# mcu.net
KiCad netlist of a schematic drawn in Altium Designer
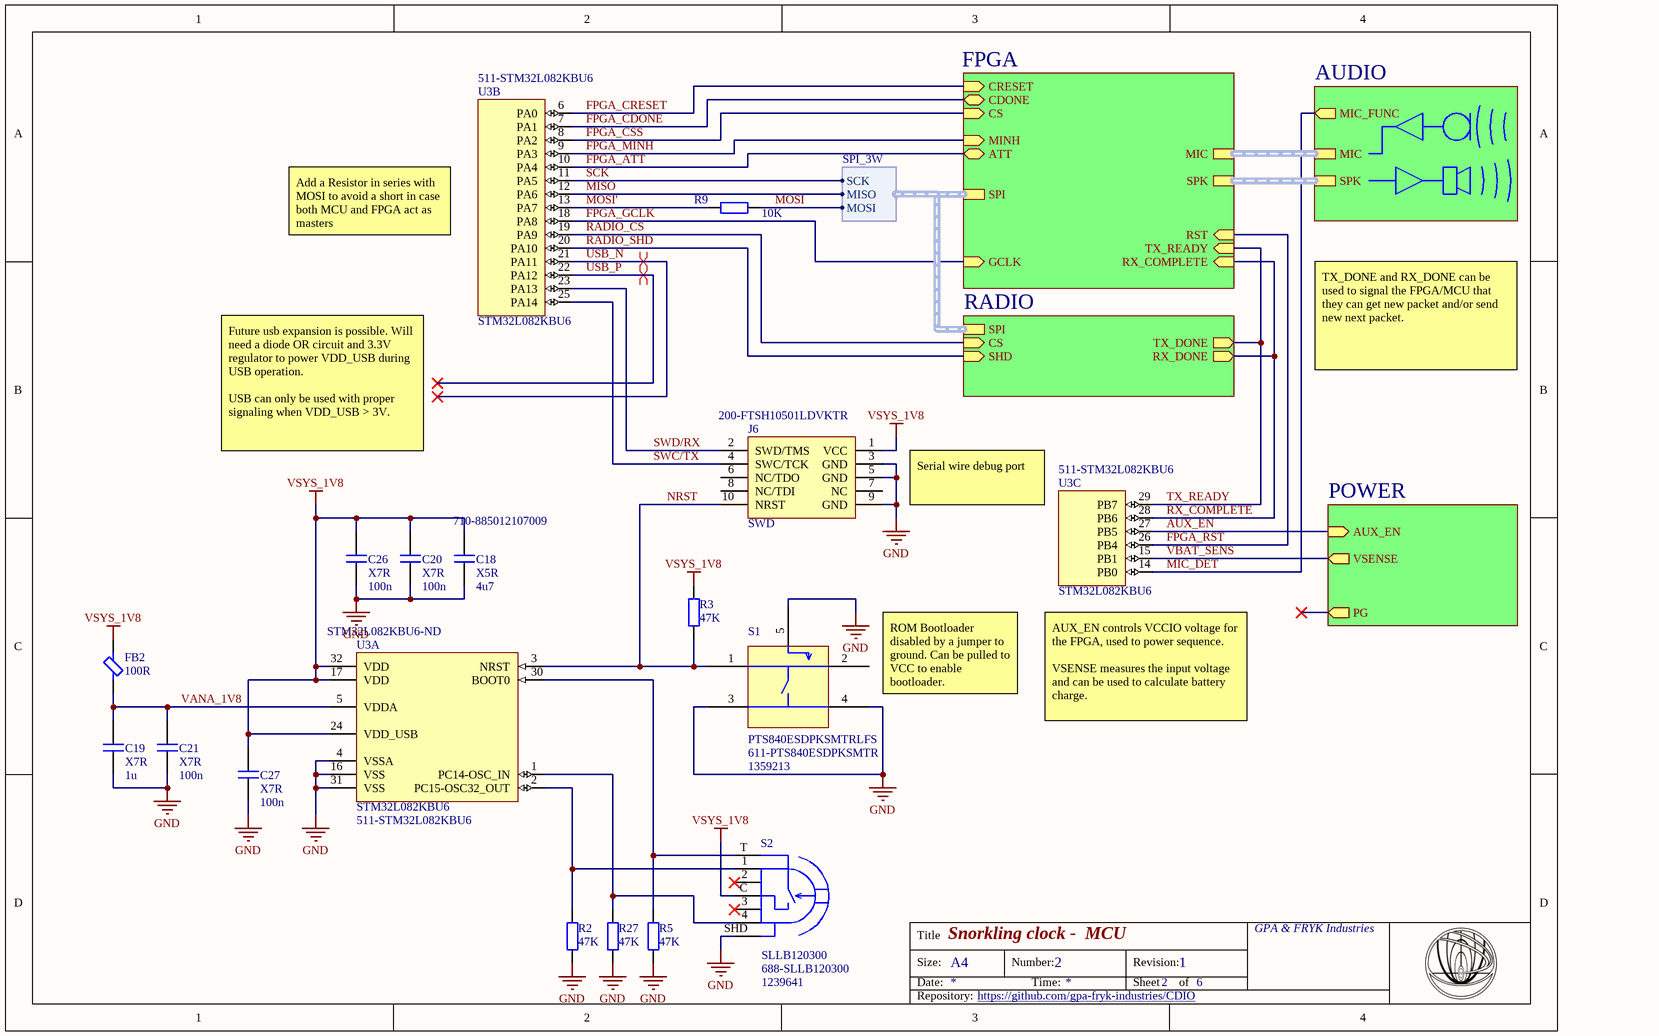
[diagram p0: mcu.SchDoc]

(export (version "E")
  (design (tool "Eeschema 10.0.6"))
  (components
    (comp (ref "C18")
      (value "4u7")
      (footprint "CAPC2012X11N")
      (description "Capacitor")
      (fields
        (field (name "TYPE") "X5R")
        (field (name "SUPPLIER PART NUMBER 1") "710-885012107009")
        (field (name "Comment") "cap")
      )
      (libsource (lib "lib_passives") (part "cap"))
    )
    (comp (ref "C19")
      (value "1u")
      (footprint "CAPC2012X11N")
      (description "Capacitor")
      (fields (field (name "TYPE") "X7R") (field (name "Comment") "cap"))
      (libsource (lib "lib_passives") (part "cap"))
    )
    (comp (ref "C20")
      (value "100n")
      (footprint "CAPC1005X06N")
      (description "Capacitor")
      (fields (field (name "TYPE") "X7R") (field (name "Comment") "cap"))
      (libsource (lib "lib_passives") (part "cap"))
    )
    (comp (ref "C21")
      (value "100n")
      (footprint "CAPC1005X06N")
      (description "Capacitor")
      (fields (field (name "TYPE") "X7R") (field (name "Comment") "cap"))
      (libsource (lib "lib_passives") (part "cap"))
    )
    (comp (ref "C26")
      (value "100n")
      (footprint "CAPC1005X06N")
      (description "Capacitor")
      (fields (field (name "TYPE") "X7R") (field (name "Comment") "cap"))
      (libsource (lib "lib_passives") (part "cap"))
    )
    (comp (ref "C27")
      (value "100n")
      (footprint "CAPC1005X06N")
      (description "Capacitor")
      (fields (field (name "TYPE") "X7R") (field (name "Comment") "cap"))
      (libsource (lib "lib_passives") (part "cap"))
    )
    (comp (ref "FB2")
      (value "100R")
      (footprint "INDC1005X06N")
      (description "Inductor")
      (fields (field (name "Comment") "ferrite"))
      (libsource (lib "lib_passives") (part "ferrite"))
    )
    (comp (ref "J6")
      (value "SWD")
      (footprint "hdr_2x5_50mil")
      (description "SWD Header")
      (fields (field (name "SUPPLIER PART NUMBER 1") "200-FTSH10501LDVKTR"))
      (libsource (lib "lib_connectors") (part "hdr_swd"))
    )
    (comp (ref "R2")
      (value "47K")
      (footprint "RESC1005X04N")
      (description "Resistor")
      (fields (field (name "Comment") "res"))
      (libsource (lib "lib_passives") (part "res"))
    )
    (comp (ref "R3")
      (value "47K")
      (footprint "RESC1005X04N")
      (description "Resistor")
      (fields (field (name "Comment") "res"))
      (libsource (lib "lib_passives") (part "res"))
    )
    (comp (ref "R5")
      (value "47K")
      (footprint "RESC1005X04N")
      (description "Resistor")
      (fields (field (name "Comment") "res"))
      (libsource (lib "lib_passives") (part "res"))
    )
    (comp (ref "R9")
      (value "10K")
      (footprint "RESC1005X04N")
      (description "Resistor")
      (fields (field (name "Comment") "res"))
      (libsource (lib "") (part "res_1"))
    )
    (comp (ref "R27")
      (value "47K")
      (footprint "RESC1005X04N")
      (description "Resistor")
      (fields (field (name "Comment") "res"))
      (libsource (lib "lib_passives") (part "res"))
    )
    (comp (ref "S1")
      (value "PTS840ESDPKSMTRLFS")
      (footprint "PCBComponent_1")
      (description "Microminiature SMT Side Actuated tactile switch")
      (fields
        (field (name "SUPPLIER PART NUMBER 1") "611-PTS840ESDPKSMTR")
        (field (name "SUPPLIER PART NUMBER 2") "1359213")
      )
      (libsource (lib "lib_cnk") (part "pts840esdpksmtrlfs"))
    )
    (comp (ref "S2")
      (value "SLLB120300")
      (footprint "sllb120300")
      (description "Compact and low-profile horizontal type for various applications")
      (fields
        (field (name "SUPPLIER PART NUMBER 1") "688-SLLB120300")
        (field (name "SUPPLIER PART NUMBER 2") "1239641")
      )
      (libsource (lib "lib_alps") (part "sllb120300"))
    )
    (comp (ref "U3")
      (value "STM32L082KBU6")
      (footprint "QFN50P500X500X60_HS-33N")
      (fields
        (field (name "SUPPLIER PART NUMBER 1") "511-STM32L082KBU6")
        (field (name "SUPPLIER PART NUMBER 2") "STM32L082KBU6-ND")
      )
      (libsource (lib "") (part "stm32l082kbu6_1"))
    )
  )
  (nets
    (net (code "2") (name "/AUX_EN") (class "Default")
      (node (ref "U3") (pin "27") (pinfunction "PB5_27") (pintype "bidirectional"))
    )
    (net (code "3") (name "/FPGA_ATT") (class "Default")
      (node (ref "U3") (pin "10") (pinfunction "PA4_10") (pintype "bidirectional"))
    )
    (net (code "4") (name "/FPGA_CDONE") (class "Default")
      (node (ref "U3") (pin "7") (pinfunction "PA1_7") (pintype "bidirectional"))
    )
    (net (code "5") (name "/FPGA_CRESET") (class "Default")
      (node (ref "U3") (pin "6") (pinfunction "PA0_6") (pintype "bidirectional"))
    )
    (net (code "6") (name "/FPGA_CSS") (class "Default")
      (node (ref "U3") (pin "8") (pinfunction "PA2_8") (pintype "bidirectional"))
    )
    (net (code "7") (name "/FPGA_GCLK") (class "Default")
      (node (ref "U3") (pin "18") (pinfunction "PA8_18") (pintype "bidirectional"))
    )
    (net (code "8") (name "/FPGA_MINH") (class "Default")
      (node (ref "U3") (pin "9") (pinfunction "PA3_9") (pintype "bidirectional"))
    )
    (net (code "9") (name "/FPGA_RST") (class "Default")
      (node (ref "U3") (pin "26") (pinfunction "PB4_26") (pintype "bidirectional"))
    )
    (net (code "10") (name "/MIC_DET") (class "Default")
      (node (ref "U3") (pin "14") (pinfunction "PB0_14") (pintype "bidirectional"))
    )
    (net (code "12") (name "/MISO") (class "Default")
      (node (ref "U3") (pin "12") (pinfunction "PA6_12") (pintype "bidirectional"))
    )
    (net (code "13") (name "/MOSI") (class "Default")
      (node (ref "R9") (pin "2") (pinfunction "2_2") (pintype "passive"))
    )
    (net (code "14") (name "/MOSI'") (class "Default")
      (node (ref "R9") (pin "1") (pinfunction "1_1") (pintype "passive"))
      (node (ref "U3") (pin "13") (pinfunction "PA7_13") (pintype "bidirectional"))
    )
    (net (code "15") (name "/NRST") (class "Default")
      (node (ref "J6") (pin "10") (pinfunction "NRST_10") (pintype "passive"))
      (node (ref "R3") (pin "1") (pinfunction "1_1") (pintype "passive"))
      (node (ref "S1") (pin "1") (pintype "passive"))
      (node (ref "U3") (pin "3") (pinfunction "NRST_3") (pintype "input"))
    )
    (net (code "17") (name "/RADIO_CS") (class "Default")
      (node (ref "U3") (pin "19") (pinfunction "PA9_19") (pintype "bidirectional"))
    )
    (net (code "18") (name "/RADIO_SHD") (class "Default")
      (node (ref "U3") (pin "20") (pinfunction "PA10_20") (pintype "bidirectional"))
    )
    (net (code "19") (name "/RX_COMPLETE") (class "Default")
      (node (ref "U3") (pin "28") (pinfunction "PB6_28") (pintype "bidirectional"))
    )
    (net (code "20") (name "/SCK") (class "Default")
      (node (ref "U3") (pin "11") (pinfunction "PA5_11") (pintype "bidirectional"))
    )
    (net (code "22") (name "/SWC{slash}TX") (class "Default")
      (node (ref "J6") (pin "4") (pinfunction "SWC/TCK_4") (pintype "passive"))
      (node (ref "U3") (pin "25") (pinfunction "PA14_25") (pintype "bidirectional"))
    )
    (net (code "23") (name "/SWD{slash}RX") (class "Default")
      (node (ref "J6") (pin "2") (pinfunction "SWD/TMS_2") (pintype "passive"))
      (node (ref "U3") (pin "23") (pinfunction "PA13_23") (pintype "bidirectional"))
    )
    (net (code "24") (name "/TX_READY") (class "Default")
      (node (ref "U3") (pin "29") (pinfunction "PB7_29") (pintype "bidirectional"))
    )
    (net (code "25") (name "/USB_N") (class "Default")
      (node (ref "U3") (pin "21") (pinfunction "PA11_21") (pintype "bidirectional+no_connect"))
    )
    (net (code "26") (name "/USB_P") (class "Default")
      (node (ref "U3") (pin "22") (pinfunction "PA12_22") (pintype "bidirectional+no_connect"))
    )
    (net (code "27") (name "/VANA_1V8") (class "Default")
      (node (ref "C19") (pin "2") (pinfunction "2_2") (pintype "passive"))
      (node (ref "C21") (pin "1") (pinfunction "1_1") (pintype "passive"))
      (node (ref "FB2") (pin "1") (pinfunction "1_1") (pintype "passive"))
      (node (ref "U3") (pin "5") (pinfunction "VDDA_5") (pintype "power_in"))
    )
    (net (code "28") (name "/VBAT_SENS") (class "Default")
      (node (ref "U3") (pin "15") (pinfunction "PB1_15") (pintype "bidirectional"))
    )
    (net (code "30") (name "GND") (class "Default")
      (node (ref "C18") (pin "1") (pinfunction "1_1") (pintype "passive"))
      (node (ref "C19") (pin "1") (pinfunction "1_1") (pintype "passive"))
      (node (ref "C20") (pin "2") (pinfunction "2_2") (pintype "passive"))
      (node (ref "C21") (pin "2") (pinfunction "2_2") (pintype "passive"))
      (node (ref "C26") (pin "2") (pinfunction "2_2") (pintype "passive"))
      (node (ref "C27") (pin "2") (pinfunction "2_2") (pintype "passive"))
      (node (ref "J6") (pin "3") (pinfunction "GND_3") (pintype "passive"))
      (node (ref "J6") (pin "5") (pinfunction "GND_5") (pintype "passive"))
      (node (ref "J6") (pin "9") (pinfunction "GND_9") (pintype "passive"))
      (node (ref "R2") (pin "1") (pinfunction "1_1") (pintype "passive"))
      (node (ref "R27") (pin "1") (pinfunction "1_1") (pintype "passive"))
      (node (ref "R5") (pin "1") (pinfunction "1_1") (pintype "passive"))
      (node (ref "S1") (pin "3") (pintype "passive"))
      (node (ref "S1") (pin "4") (pintype "passive"))
      (node (ref "S1") (pin "5") (pintype "passive"))
      (node (ref "S2") (pin "SHD") (pinfunction "SHD_SHD") (pintype "passive"))
      (node (ref "U3") (pin "16") (pinfunction "VSS_16") (pintype "power_in"))
      (node (ref "U3") (pin "31") (pinfunction "VSS_31") (pintype "power_in"))
      (node (ref "U3") (pin "4") (pinfunction "VSSA_4") (pintype "power_in"))
    )
    (net (code "31") (name "Net-(U3A-BOOT0)") (class "Default")
      (node (ref "R5") (pin "2") (pinfunction "2_2") (pintype "passive"))
      (node (ref "S2") (pin "T") (pinfunction "T_T") (pintype "passive"))
      (node (ref "U3") (pin "30") (pinfunction "BOOT0_30") (pintype "input"))
    )
    (net (code "32") (name "Net-(U3A-PC14-OSC_IN)") (class "Default")
      (node (ref "R27") (pin "2") (pinfunction "2_2") (pintype "passive"))
      (node (ref "S2") (pin "4") (pinfunction "4_4") (pintype "passive"))
      (node (ref "U3") (pin "1") (pinfunction "PC14-OSC_IN_1") (pintype "bidirectional"))
    )
    (net (code "33") (name "Net-(U3A-PC15-OSC32_OUT)") (class "Default")
      (node (ref "R2") (pin "2") (pinfunction "2_2") (pintype "passive"))
      (node (ref "S2") (pin "1") (pinfunction "1_1") (pintype "passive"))
      (node (ref "U3") (pin "2") (pinfunction "PC15-OSC32_OUT_2") (pintype "bidirectional"))
    )
    (net (code "34") (name "VSYS_1V8") (class "Default")
      (node (ref "C18") (pin "2") (pinfunction "2_2") (pintype "passive"))
      (node (ref "C20") (pin "1") (pinfunction "1_1") (pintype "passive"))
      (node (ref "C26") (pin "1") (pinfunction "1_1") (pintype "passive"))
      (node (ref "C27") (pin "1") (pinfunction "1_1") (pintype "passive"))
      (node (ref "FB2") (pin "2") (pinfunction "2_2") (pintype "passive"))
      (node (ref "J6") (pin "1") (pinfunction "VCC_1") (pintype "passive"))
      (node (ref "R3") (pin "2") (pinfunction "2_2") (pintype "passive"))
      (node (ref "S2") (pin "C") (pinfunction "C_C") (pintype "passive"))
      (node (ref "U3") (pin "17") (pinfunction "VDD_17") (pintype "power_in"))
      (node (ref "U3") (pin "24") (pinfunction "VDD_USB_24") (pintype "power_in"))
      (node (ref "U3") (pin "32") (pinfunction "VDD_32") (pintype "power_in"))
    )
    (net (code "35") (name "unconnected-(J6-NC-Pad7)") (class "Default")
      (node (ref "J6") (pin "7") (pinfunction "NC_7") (pintype "passive"))
    )
    (net (code "36") (name "unconnected-(J6-NC{slash}TDI-Pad8)") (class "Default")
      (node (ref "J6") (pin "8") (pinfunction "NC/TDI_8") (pintype "passive"))
    )
    (net (code "37") (name "unconnected-(J6-NC{slash}TDO-Pad6)") (class "Default")
      (node (ref "J6") (pin "6") (pinfunction "NC/TDO_6") (pintype "passive"))
    )
    (net (code "38") (name "unconnected-(S1-Pad2)") (class "Default")
      (node (ref "S1") (pin "2") (pintype "passive"))
    )
    (net (code "39") (name "unconnected-(S2-Pad2)") (class "Default")
      (node (ref "S2") (pin "2") (pinfunction "2_2") (pintype "passive+no_connect"))
    )
    (net (code "40") (name "unconnected-(S2-Pad3)") (class "Default")
      (node (ref "S2") (pin "3") (pinfunction "3_3") (pintype "passive+no_connect"))
    )
  )
)
